# DC-DC_SY8029AIC.net
KiCad netlist of a schematic drawn in Altium Designer
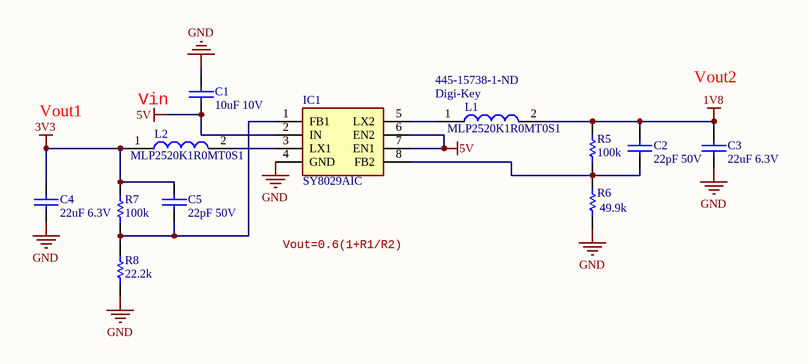
[diagram p0: DC-DC SY8029AIC.SchDoc]

(export (version "E")
  (design (tool "Eeschema 10.0.6"))
  (components
    (comp (ref "C1")
      (value "10uF 10V")
      (footprint "Capacitance:0805C")
      (libsource (lib "电容") (part "CAP-NP"))
    )
    (comp (ref "C2")
      (value "22pF 50V")
      (footprint "Capacitance:0402C")
      (libsource (lib "电容") (part "CAP-NP"))
    )
    (comp (ref "C3")
      (value "22uF 6.3V")
      (footprint "Capacitance:0603C")
      (libsource (lib "电容") (part "CAP-NP"))
    )
    (comp (ref "C4")
      (value "22uF 6.3V")
      (footprint "Capacitance:0603C")
      (libsource (lib "电容") (part "CAP-NP"))
    )
    (comp (ref "C5")
      (value "22pF 50V")
      (footprint "Capacitance:0402C")
      (libsource (lib "电容") (part "CAP-NP"))
    )
    (comp (ref "IC1")
      (value "SY8029AIC")
      (footprint "SamacSys:SOT65P280X110-8N")
      (description "Integrated Circuit")
      (libsource (lib "*") (part "SY8029AIC"))
    )
    (comp (ref "L1")
      (value "MLP2520K1R0MT0S1")
      (footprint "SamacSys:INDC2520X100N")
      (description "Inductor")
      (fields
        (field (name "MOUSER PART NUMBER") "810-MLP2520K1R0MT0S1")
        (field (name "SUPPLIER 1") "Digi-Key")
        (field (name "SUPPLIER PART NUMBER 1") "445-15738-1-ND")
      )
      (libsource (lib "*") (part "MLP2520K1R0MT0S1"))
    )
    (comp (ref "L2")
      (value "MLP2520K1R0MT0S1")
      (footprint "SamacSys:INDC2520X100N")
      (description "Inductor")
      (fields (field (name "MOUSER PART NUMBER") "810-MLP2520K1R0MT0S1"))
      (libsource (lib "*") (part "MLP2520K1R0MT0S1"))
    )
    (comp (ref "R5") (value "100k") (footprint "0402R") (libsource (lib "电阻") (part "RES")))
    (comp (ref "R6") (value "49.9k") (footprint "0402R") (libsource (lib "电阻") (part "RES")))
    (comp (ref "R7") (value "100k") (footprint "0402R") (libsource (lib "电阻") (part "RES")))
    (comp (ref "R8") (value "22.2k") (footprint "0402R") (libsource (lib "电阻") (part "RES")))
  )
  (nets
    (net (code "1") (name "1V8") (class "Default")
      (node (ref "C2") (pin "2") (pinfunction "2_2") (pintype "passive"))
      (node (ref "C3") (pin "2") (pinfunction "2_2") (pintype "passive"))
      (node (ref "L1") (pin "2") (pinfunction "2_2") (pintype "passive"))
      (node (ref "R5") (pin "2") (pinfunction "2_2") (pintype "passive"))
    )
    (net (code "2") (name "3V3") (class "Default")
      (node (ref "C4") (pin "2") (pinfunction "2_2") (pintype "passive"))
      (node (ref "C5") (pin "2") (pinfunction "2_2") (pintype "passive"))
      (node (ref "L2") (pin "1") (pinfunction "1_1") (pintype "passive"))
      (node (ref "R7") (pin "2") (pinfunction "2_2") (pintype "passive"))
    )
    (net (code "3") (name "5V") (class "Default")
      (node (ref "C1") (pin "1") (pinfunction "1_1") (pintype "passive"))
      (node (ref "IC1") (pin "2") (pinfunction "IN_2") (pintype "passive"))
      (node (ref "IC1") (pin "6") (pinfunction "EN2_6") (pintype "passive"))
      (node (ref "IC1") (pin "7") (pinfunction "EN1_7") (pintype "passive"))
    )
    (net (code "4") (name "GND") (class "Default")
      (node (ref "C1") (pin "2") (pinfunction "2_2") (pintype "passive"))
      (node (ref "C3") (pin "1") (pinfunction "1_1") (pintype "passive"))
      (node (ref "C4") (pin "1") (pinfunction "1_1") (pintype "passive"))
      (node (ref "IC1") (pin "4") (pinfunction "GND_4") (pintype "passive"))
      (node (ref "R6") (pin "1") (pinfunction "1_1") (pintype "passive"))
      (node (ref "R8") (pin "1") (pinfunction "1_1") (pintype "passive"))
    )
    (net (code "5") (name "Net-(IC1-FB1)") (class "Default")
      (node (ref "C5") (pin "1") (pinfunction "1_1") (pintype "passive"))
      (node (ref "IC1") (pin "1") (pinfunction "FB1_1") (pintype "passive"))
      (node (ref "R7") (pin "1") (pinfunction "1_1") (pintype "passive"))
      (node (ref "R8") (pin "2") (pinfunction "2_2") (pintype "passive"))
    )
    (net (code "6") (name "Net-(IC1-FB2)") (class "Default")
      (node (ref "C2") (pin "1") (pinfunction "1_1") (pintype "passive"))
      (node (ref "IC1") (pin "8") (pinfunction "FB2_8") (pintype "passive"))
      (node (ref "R5") (pin "1") (pinfunction "1_1") (pintype "passive"))
      (node (ref "R6") (pin "2") (pinfunction "2_2") (pintype "passive"))
    )
    (net (code "7") (name "Net-(IC1-LX1)") (class "Default")
      (node (ref "IC1") (pin "3") (pinfunction "LX1_3") (pintype "passive"))
      (node (ref "L2") (pin "2") (pinfunction "2_2") (pintype "passive"))
    )
    (net (code "8") (name "Net-(IC1-LX2)") (class "Default")
      (node (ref "IC1") (pin "5") (pinfunction "LX2_5") (pintype "passive"))
      (node (ref "L1") (pin "1") (pinfunction "1_1") (pintype "passive"))
    )
  )
)
